# communication.net
KiCad netlist of a schematic drawn in Altium Designer
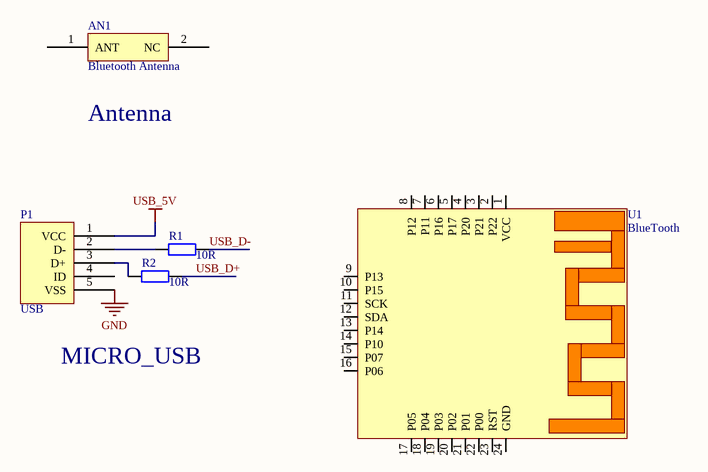
[diagram p0: communication.SchDoc]

(export (version "E")
  (design (tool "Eeschema 10.0.6"))
  (components
    (comp (ref "AN1")
      (value "Bluetooth Antenna")
      (footprint "AN9520")
      (libsource (lib "quadcopter") (part "AN9520"))
    )
    (comp (ref "P1") (value "USB") (footprint "USB_MICRO_M") (libsource (lib "mcu_board") (part "USB")))
    (comp (ref "R1")
      (value "10R")
      (footprint "R-0603")
      (description "Resistor")
      (fields (field (name "Comment") "Res2") (field (name "PUBLISHER") "Altium Limited"))
      (libsource (lib "Miscellaneous Devices") (part "Res2"))
    )
    (comp (ref "R2")
      (value "10R")
      (footprint "AXIAL-0.4")
      (description "Resistor")
      (fields (field (name "Comment") "Res2") (field (name "PUBLISHER") "Altium Limited"))
      (libsource (lib "Miscellaneous Devices") (part "Res2"))
    )
    (comp (ref "U1")
      (value "BlueTooth")
      (footprint "BLE_CC2541")
      (libsource (lib "mcu_board") (part "CC2541-MOD"))
    )
  )
  (nets
    (net (code "1") (name "/USB_D+") (class "Default")
      (node (ref "R2") (pin "2") (pinfunction "2_2") (pintype "passive"))
    )
    (net (code "2") (name "/USB_D-") (class "Default")
      (node (ref "R1") (pin "2") (pinfunction "2_2") (pintype "passive"))
    )
    (net (code "3") (name "GND") (class "Default")
      (node (ref "P1") (pin "5") (pinfunction "VSS_5") (pintype "passive"))
    )
    (net (code "4") (name "Net-(P1-D+)") (class "Default")
      (node (ref "P1") (pin "3") (pinfunction "D+_3") (pintype "passive"))
      (node (ref "R2") (pin "1") (pinfunction "1_1") (pintype "passive"))
    )
    (net (code "5") (name "Net-(P1-D-)") (class "Default")
      (node (ref "P1") (pin "2") (pinfunction "D-_2") (pintype "passive"))
      (node (ref "R1") (pin "1") (pinfunction "1_1") (pintype "passive"))
    )
    (net (code "6") (name "USB_5V") (class "Default")
      (node (ref "P1") (pin "1") (pinfunction "VCC_1") (pintype "passive"))
    )
    (net (code "7") (name "unconnected-(AN1-ANT-Pad1)") (class "Default")
      (node (ref "AN1") (pin "1") (pinfunction "ANT_1") (pintype "passive"))
    )
    (net (code "8") (name "unconnected-(AN1-NC-Pad2)") (class "Default")
      (node (ref "AN1") (pin "2") (pinfunction "NC_2") (pintype "passive"))
    )
    (net (code "9") (name "unconnected-(P1-ID-Pad4)") (class "Default")
      (node (ref "P1") (pin "4") (pinfunction "ID_4") (pintype "passive"))
    )
    (net (code "10") (name "unconnected-(U1-GND-Pad24)") (class "Default")
      (node (ref "U1") (pin "24") (pinfunction "GND_24") (pintype "passive"))
    )
    (net (code "11") (name "unconnected-(U1-P00-Pad22)") (class "Default")
      (node (ref "U1") (pin "22") (pinfunction "P00_22") (pintype "passive"))
    )
    (net (code "12") (name "unconnected-(U1-P01-Pad21)") (class "Default")
      (node (ref "U1") (pin "21") (pinfunction "P01_21") (pintype "passive"))
    )
    (net (code "13") (name "unconnected-(U1-P02-Pad20)") (class "Default")
      (node (ref "U1") (pin "20") (pinfunction "P02_20") (pintype "passive"))
    )
    (net (code "14") (name "unconnected-(U1-P03-Pad19)") (class "Default")
      (node (ref "U1") (pin "19") (pinfunction "P03_19") (pintype "passive"))
    )
    (net (code "15") (name "unconnected-(U1-P04-Pad18)") (class "Default")
      (node (ref "U1") (pin "18") (pinfunction "P04_18") (pintype "passive"))
    )
    (net (code "16") (name "unconnected-(U1-P05-Pad17)") (class "Default")
      (node (ref "U1") (pin "17") (pinfunction "P05_17") (pintype "passive"))
    )
    (net (code "17") (name "unconnected-(U1-P06-Pad16)") (class "Default")
      (node (ref "U1") (pin "16") (pinfunction "P06_16") (pintype "passive"))
    )
    (net (code "18") (name "unconnected-(U1-P07-Pad15)") (class "Default")
      (node (ref "U1") (pin "15") (pinfunction "P07_15") (pintype "passive"))
    )
    (net (code "19") (name "unconnected-(U1-P10-Pad14)") (class "Default")
      (node (ref "U1") (pin "14") (pinfunction "P10_14") (pintype "passive"))
    )
    (net (code "20") (name "unconnected-(U1-P11-Pad7)") (class "Default")
      (node (ref "U1") (pin "7") (pinfunction "P11_7") (pintype "passive"))
    )
    (net (code "21") (name "unconnected-(U1-P12-Pad8)") (class "Default")
      (node (ref "U1") (pin "8") (pinfunction "P12_8") (pintype "passive"))
    )
    (net (code "22") (name "unconnected-(U1-P13-Pad9)") (class "Default")
      (node (ref "U1") (pin "9") (pinfunction "P13_9") (pintype "passive"))
    )
    (net (code "23") (name "unconnected-(U1-P14-Pad13)") (class "Default")
      (node (ref "U1") (pin "13") (pinfunction "P14_13") (pintype "passive"))
    )
    (net (code "24") (name "unconnected-(U1-P15-Pad10)") (class "Default")
      (node (ref "U1") (pin "10") (pinfunction "P15_10") (pintype "passive"))
    )
    (net (code "25") (name "unconnected-(U1-P16-Pad6)") (class "Default")
      (node (ref "U1") (pin "6") (pinfunction "P16_6") (pintype "passive"))
    )
    (net (code "26") (name "unconnected-(U1-P17-Pad5)") (class "Default")
      (node (ref "U1") (pin "5") (pinfunction "P17_5") (pintype "passive"))
    )
    (net (code "27") (name "unconnected-(U1-P20-Pad4)") (class "Default")
      (node (ref "U1") (pin "4") (pinfunction "P20_4") (pintype "passive"))
    )
    (net (code "28") (name "unconnected-(U1-P21-Pad3)") (class "Default")
      (node (ref "U1") (pin "3") (pinfunction "P21_3") (pintype "passive"))
    )
    (net (code "29") (name "unconnected-(U1-P22-Pad2)") (class "Default")
      (node (ref "U1") (pin "2") (pinfunction "P22_2") (pintype "passive"))
    )
    (net (code "30") (name "unconnected-(U1-RST-Pad23)") (class "Default")
      (node (ref "U1") (pin "23") (pinfunction "RST_23") (pintype "passive"))
    )
    (net (code "31") (name "unconnected-(U1-SCK-Pad11)") (class "Default")
      (node (ref "U1") (pin "11") (pinfunction "SCK_11") (pintype "passive"))
    )
    (net (code "32") (name "unconnected-(U1-SDA-Pad12)") (class "Default")
      (node (ref "U1") (pin "12") (pinfunction "SDA_12") (pintype "passive"))
    )
    (net (code "33") (name "unconnected-(U1-VCC-Pad1)") (class "Default")
      (node (ref "U1") (pin "1") (pinfunction "VCC_1") (pintype "passive"))
    )
  )
)
